# Gamma_PIN_V2.net
KiCad netlist of a schematic drawn in EAGLE
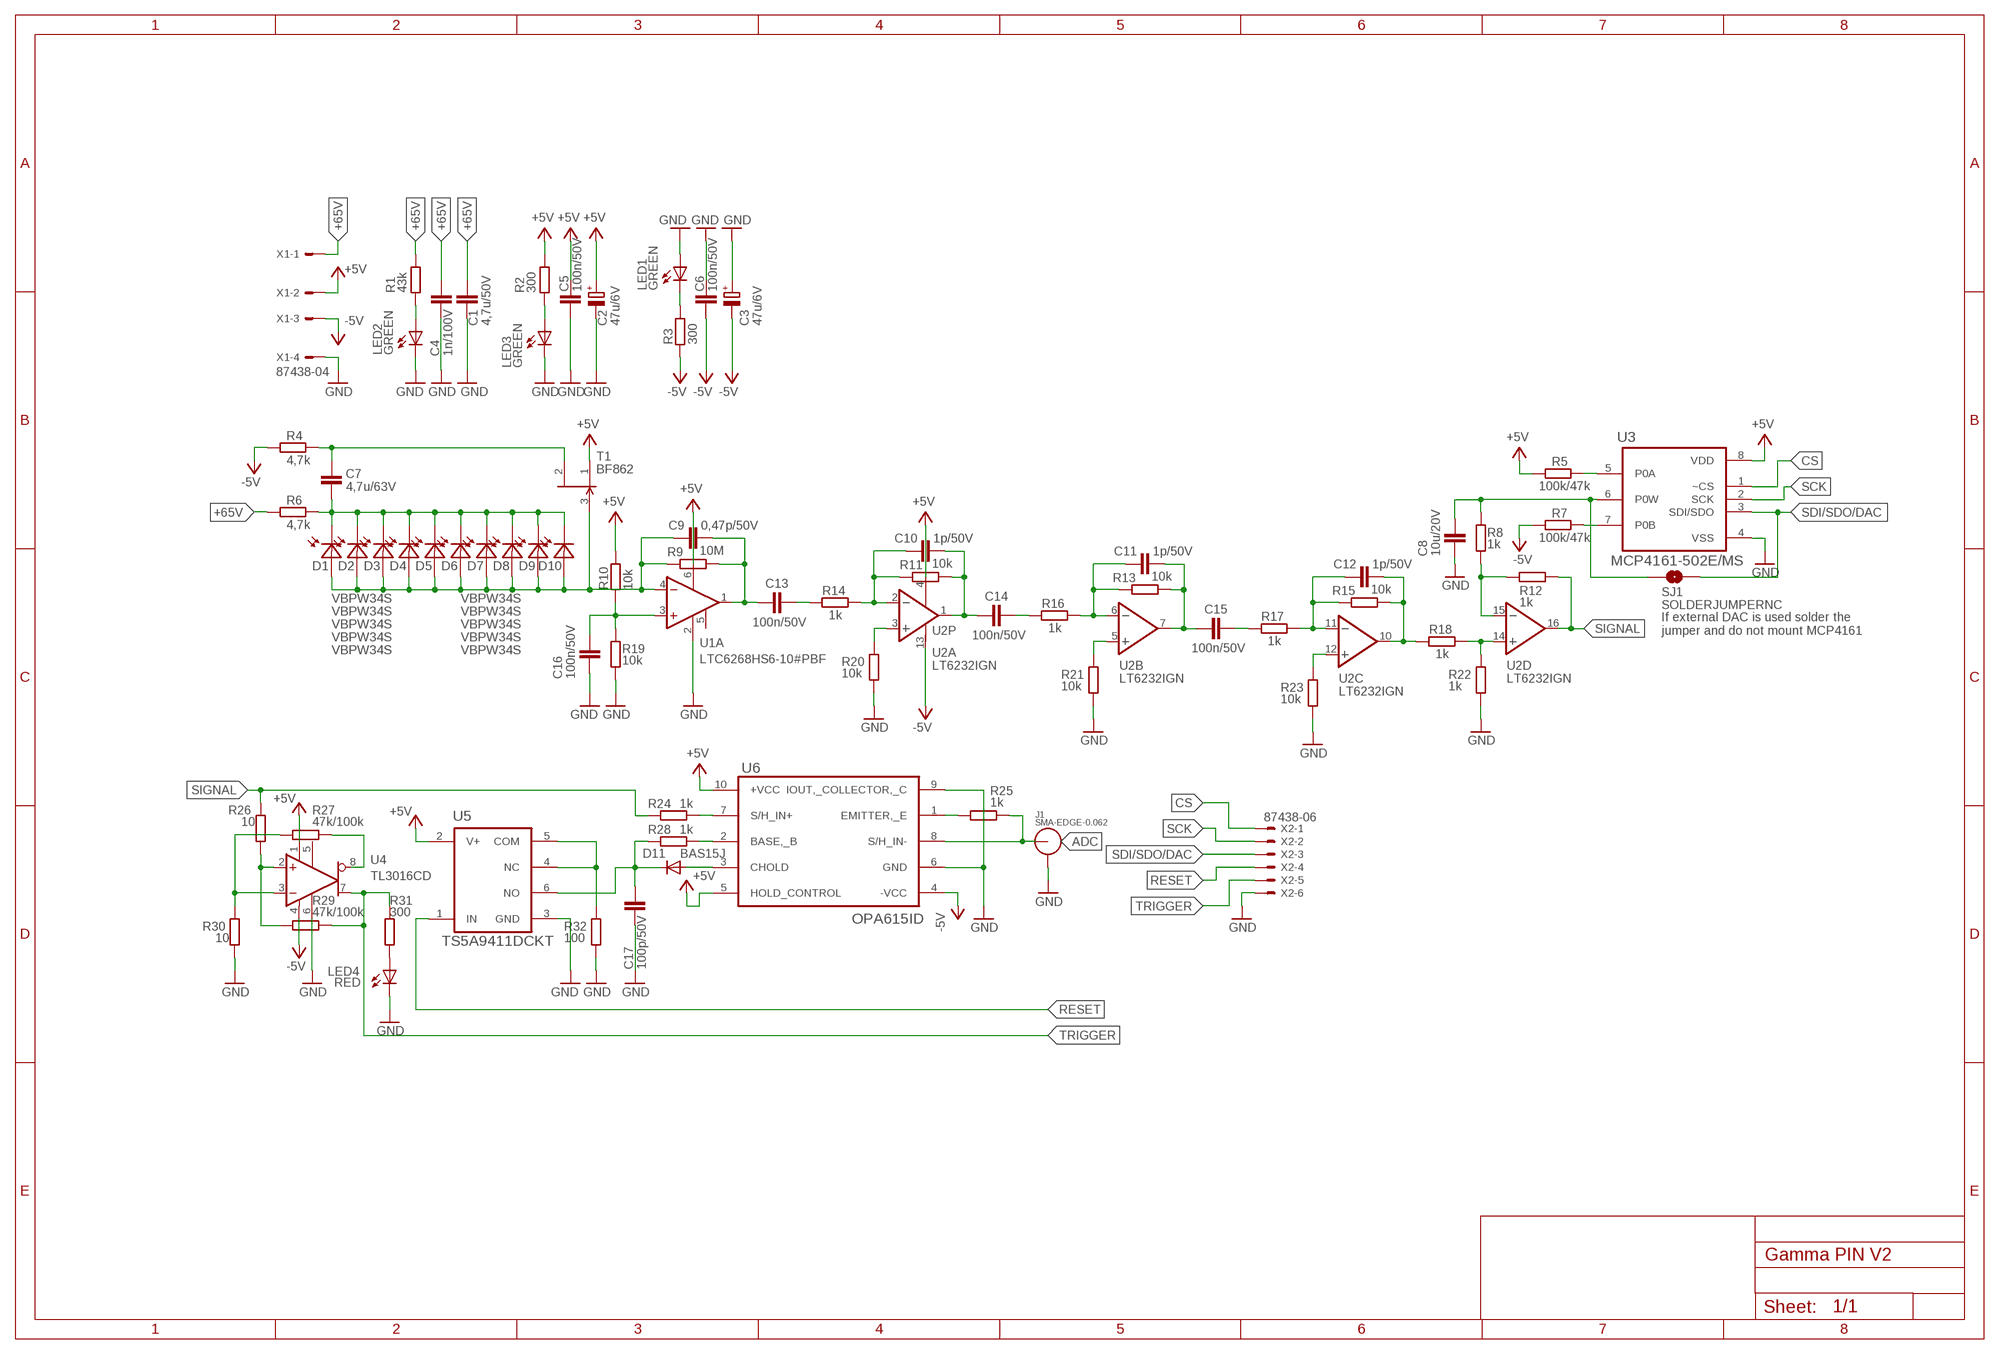
[diagram p0: schematic, sheet 1]

(export (version "E")
  (design (tool "Eeschema 10.0.6"))
  (components
    (comp (ref "C1")
      (value "4,7u/50V")
      (footprint "eagle-import:C1206")
      (libsource (lib "eagle-import") (part "rcl_334_C-EUC1206"))
    )
    (comp (ref "C2")
      (value "47u/6V")
      (footprint "eagle-import:SMC_B")
      (libsource (lib "eagle-import") (part "CPOL-EUSMCB"))
    )
    (comp (ref "C3")
      (value "47u/6V")
      (footprint "eagle-import:SMC_B")
      (libsource (lib "eagle-import") (part "CPOL-EUSMCB"))
    )
    (comp (ref "C4")
      (value "1n/100V")
      (footprint "eagle-import:C0603")
      (libsource (lib "eagle-import") (part "C-EUC0603"))
    )
    (comp (ref "C5")
      (value "100n/50V")
      (footprint "eagle-import:C0603")
      (libsource (lib "eagle-import") (part "rcl_334_C-EUC0603"))
    )
    (comp (ref "C6")
      (value "100n/50V")
      (footprint "eagle-import:C0603")
      (libsource (lib "eagle-import") (part "rcl_334_C-EUC0603"))
    )
    (comp (ref "C7")
      (value "4,7u/63V")
      (footprint "eagle-import:C1206")
      (libsource (lib "eagle-import") (part "C-EUC1206"))
    )
    (comp (ref "C8")
      (value "10u/20V")
      (footprint "eagle-import:C0603")
      (libsource (lib "eagle-import") (part "rcl_334_C-EUC0603"))
    )
    (comp (ref "C9")
      (value "0,47p/50V")
      (footprint "eagle-import:C0603")
      (libsource (lib "eagle-import") (part "rcl_334_C-EUC0603"))
    )
    (comp (ref "C10")
      (value "1p/50V")
      (footprint "eagle-import:C0603")
      (libsource (lib "eagle-import") (part "rcl_334_C-EUC0603"))
    )
    (comp (ref "C11")
      (value "1p/50V")
      (footprint "eagle-import:C0603")
      (libsource (lib "eagle-import") (part "rcl_334_C-EUC0603"))
    )
    (comp (ref "C12")
      (value "1p/50V")
      (footprint "eagle-import:C0603")
      (libsource (lib "eagle-import") (part "rcl_334_C-EUC0603"))
    )
    (comp (ref "C13")
      (value "100n/50V")
      (footprint "eagle-import:C0603")
      (libsource (lib "eagle-import") (part "rcl_334_C-EUC0603"))
    )
    (comp (ref "C14")
      (value "100n/50V")
      (footprint "eagle-import:C0603")
      (libsource (lib "eagle-import") (part "rcl_334_C-EUC0603"))
    )
    (comp (ref "C15")
      (value "100n/50V")
      (footprint "eagle-import:C0603")
      (libsource (lib "eagle-import") (part "rcl_334_C-EUC0603"))
    )
    (comp (ref "C16")
      (value "100n/50V")
      (footprint "eagle-import:C0603")
      (libsource (lib "eagle-import") (part "rcl_334_C-EUC0603"))
    )
    (comp (ref "C17")
      (value "100p/50V")
      (footprint "eagle-import:C0603")
      (libsource (lib "eagle-import") (part "rcl_334_C-EUC0603"))
    )
    (comp (ref "D1")
      (value "VBPW34S")
      (footprint "eagle-import:SOD6439X130N")
      (fields (field (name "MF") "Vishay"))
      (libsource (lib "eagle-import") (part "VBPW34S"))
    )
    (comp (ref "D2")
      (value "VBPW34S")
      (footprint "eagle-import:SOD6439X130N")
      (fields (field (name "MF") "Vishay"))
      (libsource (lib "eagle-import") (part "VBPW34S"))
    )
    (comp (ref "D3")
      (value "VBPW34S")
      (footprint "eagle-import:SOD6439X130N")
      (fields (field (name "MF") "Vishay"))
      (libsource (lib "eagle-import") (part "VBPW34S"))
    )
    (comp (ref "D4")
      (value "VBPW34S")
      (footprint "eagle-import:SOD6439X130N")
      (fields (field (name "MF") "Vishay"))
      (libsource (lib "eagle-import") (part "VBPW34S"))
    )
    (comp (ref "D5")
      (value "VBPW34S")
      (footprint "eagle-import:SOD6439X130N")
      (fields (field (name "MF") "Vishay"))
      (libsource (lib "eagle-import") (part "VBPW34S"))
    )
    (comp (ref "D6")
      (value "VBPW34S")
      (footprint "eagle-import:SOD6439X130N")
      (fields (field (name "MF") "Vishay"))
      (libsource (lib "eagle-import") (part "VBPW34S"))
    )
    (comp (ref "D7")
      (value "VBPW34S")
      (footprint "eagle-import:SOD6439X130N")
      (fields (field (name "MF") "Vishay"))
      (libsource (lib "eagle-import") (part "VBPW34S"))
    )
    (comp (ref "D8")
      (value "VBPW34S")
      (footprint "eagle-import:SOD6439X130N")
      (fields (field (name "MF") "Vishay"))
      (libsource (lib "eagle-import") (part "VBPW34S"))
    )
    (comp (ref "D9")
      (value "VBPW34S")
      (footprint "eagle-import:SOD6439X130N")
      (fields (field (name "MF") "Vishay"))
      (libsource (lib "eagle-import") (part "VBPW34S"))
    )
    (comp (ref "D10")
      (value "VBPW34S")
      (footprint "eagle-import:SOD6439X130N")
      (fields (field (name "MF") "Vishay"))
      (libsource (lib "eagle-import") (part "VBPW34S"))
    )
    (comp (ref "D11")
      (value "BAS15J")
      (footprint "eagle-import:SC79_INFINEON")
      (libsource (lib "eagle-import") (part "DIODE-SC79_INFINEON"))
    )
    (comp (ref "J1")
      (value "SMA-EDGE-0.062")
      (footprint "eagle-import:CONSMA003.062")
      (libsource (lib "eagle-import") (part "LINX-SMA-EDGE-0.062"))
    )
    (comp (ref "LED1")
      (value "GREEN")
      (footprint "eagle-import:CHIPLED_0603")
      (libsource (lib "eagle-import") (part "LEDCHIPLED_0603"))
    )
    (comp (ref "LED2")
      (value "GREEN")
      (footprint "eagle-import:CHIPLED_0603")
      (libsource (lib "eagle-import") (part "LEDCHIPLED_0603"))
    )
    (comp (ref "LED3")
      (value "GREEN")
      (footprint "eagle-import:CHIPLED_0603")
      (libsource (lib "eagle-import") (part "LEDCHIPLED_0603"))
    )
    (comp (ref "LED4")
      (value "RED")
      (footprint "eagle-import:CHIPLED_0603")
      (libsource (lib "eagle-import") (part "LEDCHIPLED_0603"))
    )
    (comp (ref "R1")
      (value "43k")
      (footprint "eagle-import:R0603")
      (libsource (lib "eagle-import") (part "R-EU_R0603"))
    )
    (comp (ref "R2")
      (value "300")
      (footprint "eagle-import:R0603")
      (libsource (lib "eagle-import") (part "R-EU_R0603"))
    )
    (comp (ref "R3")
      (value "300")
      (footprint "eagle-import:R0603")
      (libsource (lib "eagle-import") (part "R-EU_R0603"))
    )
    (comp (ref "R4")
      (value "4,7k")
      (footprint "eagle-import:R0603")
      (libsource (lib "eagle-import") (part "R-EU_R0603"))
    )
    (comp (ref "R5")
      (value "100k/47k")
      (footprint "eagle-import:R0603")
      (libsource (lib "eagle-import") (part "R-EU_R0603"))
    )
    (comp (ref "R6")
      (value "4,7k")
      (footprint "eagle-import:R0603")
      (libsource (lib "eagle-import") (part "R-EU_R0603"))
    )
    (comp (ref "R7")
      (value "100k/47k")
      (footprint "eagle-import:R0603")
      (libsource (lib "eagle-import") (part "R-EU_R0603"))
    )
    (comp (ref "R8")
      (value "1k")
      (footprint "eagle-import:R0603")
      (libsource (lib "eagle-import") (part "R-EU_R0603"))
    )
    (comp (ref "R9")
      (value "10M")
      (footprint "eagle-import:R0603")
      (libsource (lib "eagle-import") (part "R-EU_R0603"))
    )
    (comp (ref "R10")
      (value "10k")
      (footprint "eagle-import:R0603")
      (libsource (lib "eagle-import") (part "R-EU_R0603"))
    )
    (comp (ref "R11")
      (value "10k")
      (footprint "eagle-import:R0603")
      (libsource (lib "eagle-import") (part "R-EU_R0603"))
    )
    (comp (ref "R12")
      (value "1k")
      (footprint "eagle-import:R0603")
      (libsource (lib "eagle-import") (part "R-EU_R0603"))
    )
    (comp (ref "R13")
      (value "10k")
      (footprint "eagle-import:R0603")
      (libsource (lib "eagle-import") (part "R-EU_R0603"))
    )
    (comp (ref "R14")
      (value "1k")
      (footprint "eagle-import:R0603")
      (libsource (lib "eagle-import") (part "R-EU_R0603"))
    )
    (comp (ref "R15")
      (value "10k")
      (footprint "eagle-import:R0603")
      (libsource (lib "eagle-import") (part "R-EU_R0603"))
    )
    (comp (ref "R16")
      (value "1k")
      (footprint "eagle-import:R0603")
      (libsource (lib "eagle-import") (part "R-EU_R0603"))
    )
    (comp (ref "R17")
      (value "1k")
      (footprint "eagle-import:R0603")
      (libsource (lib "eagle-import") (part "R-EU_R0603"))
    )
    (comp (ref "R18")
      (value "1k")
      (footprint "eagle-import:R0603")
      (libsource (lib "eagle-import") (part "R-EU_R0603"))
    )
    (comp (ref "R19")
      (value "10k")
      (footprint "eagle-import:R0603")
      (libsource (lib "eagle-import") (part "R-EU_R0603"))
    )
    (comp (ref "R20")
      (value "10k")
      (footprint "eagle-import:R0603")
      (libsource (lib "eagle-import") (part "R-EU_R0603"))
    )
    (comp (ref "R21")
      (value "10k")
      (footprint "eagle-import:R0603")
      (libsource (lib "eagle-import") (part "R-EU_R0603"))
    )
    (comp (ref "R22")
      (value "1k")
      (footprint "eagle-import:R0603")
      (libsource (lib "eagle-import") (part "R-EU_R0603"))
    )
    (comp (ref "R23")
      (value "10k")
      (footprint "eagle-import:R0603")
      (libsource (lib "eagle-import") (part "R-EU_R0603"))
    )
    (comp (ref "R24")
      (value "1k")
      (footprint "eagle-import:R0603")
      (libsource (lib "eagle-import") (part "R-EU_R0603"))
    )
    (comp (ref "R25")
      (value "1k")
      (footprint "eagle-import:R0603")
      (libsource (lib "eagle-import") (part "R-EU_R0603"))
    )
    (comp (ref "R26")
      (value "10")
      (footprint "eagle-import:R0603")
      (libsource (lib "eagle-import") (part "R-EU_R0603"))
    )
    (comp (ref "R27")
      (value "47k/100k")
      (footprint "eagle-import:R0603")
      (libsource (lib "eagle-import") (part "R-EU_R0603"))
    )
    (comp (ref "R28")
      (value "1k")
      (footprint "eagle-import:R0603")
      (libsource (lib "eagle-import") (part "R-EU_R0603"))
    )
    (comp (ref "R29")
      (value "47k/100k")
      (footprint "eagle-import:R0603")
      (libsource (lib "eagle-import") (part "R-EU_R0603"))
    )
    (comp (ref "R30")
      (value "10")
      (footprint "eagle-import:R0603")
      (libsource (lib "eagle-import") (part "R-EU_R0603"))
    )
    (comp (ref "R31")
      (value "300")
      (footprint "eagle-import:R0603")
      (libsource (lib "eagle-import") (part "R-EU_R0603"))
    )
    (comp (ref "R32")
      (value "100")
      (footprint "eagle-import:R0603")
      (libsource (lib "eagle-import") (part "R-EU_R0603"))
    )
    (comp (ref "SJ1")
      (value "SOLDERJUMPERNC")
      (footprint "eagle-import:SJ_2S_SMALL")
      (libsource (lib "eagle-import") (part "SOLDERJUMPERNC"))
    )
    (comp (ref "T1")
      (value "BF862")
      (footprint "eagle-import:SOT23")
      (fields (field (name "MF") "NXP Semiconductors"))
      (libsource (lib "eagle-import") (part "BF862"))
    )
    (comp (ref "U1")
      (value "LTC6268HS6-10#PBF")
      (footprint "eagle-import:TSOT23-6")
      (libsource (lib "eagle-import") (part "LTC6268HS6-10#PBFTSOT-23"))
    )
    (comp (ref "U2")
      (value "LT6232IGN")
      (footprint "eagle-import:SSOP16")
      (libsource (lib "eagle-import") (part "LT6232GNI"))
    )
    (comp (ref "U3")
      (value "MCP4161-502E/MS")
      (footprint "eagle-import:MSOP8")
      (libsource (lib "eagle-import") (part "MCP4161-502E/MS"))
    )
    (comp (ref "U4")
      (value "TL3016CD")
      (footprint "eagle-import:TSSOP8")
      (libsource (lib "eagle-import") (part "TL3016CD"))
    )
    (comp (ref "U5")
      (value "TS5A9411DCKT")
      (footprint "eagle-import:SOT65P210X110-6N")
      (libsource (lib "eagle-import") (part "TS5A9411DCKT"))
    )
    (comp (ref "U6")
      (value "OPA615ID")
      (footprint "eagle-import:MSOP10")
      (libsource (lib "eagle-import") (part "OPA615ID"))
    )
    (comp (ref "X1")
      (value "87438-04")
      (footprint "eagle-import:87438-04")
      (fields (field (name "MF") "MOLEX"))
      (libsource (lib "eagle-import") (part "87438-04"))
    )
    (comp (ref "X2")
      (value "87438-06")
      (footprint "eagle-import:87438-06")
      (fields (field (name "MF") "MOLEX") (field (name "MPN") "87438-0643"))
      (libsource (lib "eagle-import") (part "87438-06"))
    )
  )
  (nets
    (net (code "1") (name "+5V") (class "Default")
      (node (ref "C2") (pin "+") (pinfunction "+_+") (pintype "passive"))
      (node (ref "C5") (pin "2") (pinfunction "2_2") (pintype "passive"))
      (node (ref "R10") (pin "2") (pinfunction "2_2") (pintype "passive"))
      (node (ref "R2") (pin "2") (pinfunction "2_2") (pintype "passive"))
      (node (ref "R5") (pin "1") (pinfunction "1_1") (pintype "passive"))
      (node (ref "T1") (pin "1") (pinfunction "S_1") (pintype "passive"))
      (node (ref "U1") (pin "6") (pinfunction "VDD_6") (pintype "power_in"))
      (node (ref "U2") (pin "4") (pinfunction "V+_4") (pintype "power_in"))
      (node (ref "U3") (pin "8") (pinfunction "VDD_8") (pintype "power_in"))
      (node (ref "U4") (pin "1") (pinfunction "V+_1") (pintype "power_in"))
      (node (ref "U5") (pin "2") (pinfunction "V+_2") (pintype "power_in"))
      (node (ref "U6") (pin "10") (pinfunction "+VCC_10") (pintype "power_in"))
      (node (ref "U6") (pin "5") (pinfunction "HOLD_CONTROL_5") (pintype "input"))
      (node (ref "X1") (pin "2") (pinfunction "S_2") (pintype "passive"))
    )
    (net (code "2") (name "+65V") (class "Default")
      (node (ref "C1") (pin "1") (pinfunction "1_1") (pintype "passive"))
      (node (ref "C4") (pin "2") (pinfunction "2_2") (pintype "passive"))
      (node (ref "R1") (pin "2") (pinfunction "2_2") (pintype "passive"))
      (node (ref "R6") (pin "1") (pinfunction "1_1") (pintype "passive"))
      (node (ref "X1") (pin "1") (pinfunction "S_1") (pintype "passive"))
    )
    (net (code "3") (name "-5V") (class "Default")
      (node (ref "C3") (pin "-") (pinfunction "-_-") (pintype "passive"))
      (node (ref "C6") (pin "1") (pinfunction "1_1") (pintype "passive"))
      (node (ref "R3") (pin "1") (pinfunction "1_1") (pintype "passive"))
      (node (ref "R4") (pin "1") (pinfunction "1_1") (pintype "passive"))
      (node (ref "R7") (pin "1") (pinfunction "1_1") (pintype "passive"))
      (node (ref "U2") (pin "13") (pinfunction "V-_13") (pintype "power_in"))
      (node (ref "U4") (pin "4") (pinfunction "V-_4") (pintype "power_in"))
      (node (ref "U6") (pin "4") (pinfunction "-VCC_4") (pintype "power_in"))
      (node (ref "X1") (pin "3") (pinfunction "S_3") (pintype "passive"))
    )
    (net (code "4") (name "ADC") (class "Default")
      (node (ref "J1") (pin "ANT") (pinfunction "ANT_ANT") (pintype "bidirectional"))
      (node (ref "R25") (pin "1") (pinfunction "1_1") (pintype "passive"))
      (node (ref "U6") (pin "8") (pinfunction "S/H_IN-_8") (pintype "passive"))
    )
    (net (code "5") (name "CS") (class "Default")
      (node (ref "U3") (pin "1") (pinfunction "~{CS}_1") (pintype "input"))
      (node (ref "X2") (pin "1") (pinfunction "S_1") (pintype "passive"))
    )
    (net (code "6") (name "GND") (class "Default")
      (node (ref "C1") (pin "2") (pinfunction "2_2") (pintype "passive"))
      (node (ref "C16") (pin "1") (pinfunction "1_1") (pintype "passive"))
      (node (ref "C17") (pin "1") (pinfunction "1_1") (pintype "passive"))
      (node (ref "C2") (pin "-") (pinfunction "-_-") (pintype "passive"))
      (node (ref "C3") (pin "+") (pinfunction "+_+") (pintype "passive"))
      (node (ref "C4") (pin "1") (pinfunction "1_1") (pintype "passive"))
      (node (ref "C5") (pin "1") (pinfunction "1_1") (pintype "passive"))
      (node (ref "C6") (pin "2") (pinfunction "2_2") (pintype "passive"))
      (node (ref "C8") (pin "2") (pinfunction "2_2") (pintype "passive"))
      (node (ref "J1") (pin "GND1") (pinfunction "P$2_GND1") (pintype "bidirectional"))
      (node (ref "J1") (pin "GND2") (pinfunction "P$2_GND2") (pintype "bidirectional"))
      (node (ref "J1") (pin "GND3") (pinfunction "P$2_GND3") (pintype "bidirectional"))
      (node (ref "J1") (pin "GND4") (pinfunction "P$2_GND4") (pintype "bidirectional"))
      (node (ref "LED1") (pin "A") (pinfunction "A_A") (pintype "passive"))
      (node (ref "LED2") (pin "C") (pinfunction "C_C") (pintype "passive"))
      (node (ref "LED3") (pin "C") (pinfunction "C_C") (pintype "passive"))
      (node (ref "LED4") (pin "C") (pinfunction "C_C") (pintype "passive"))
      (node (ref "R19") (pin "1") (pinfunction "1_1") (pintype "passive"))
      (node (ref "R20") (pin "2") (pinfunction "2_2") (pintype "passive"))
      (node (ref "R21") (pin "2") (pinfunction "2_2") (pintype "passive"))
      (node (ref "R22") (pin "2") (pinfunction "2_2") (pintype "passive"))
      (node (ref "R23") (pin "2") (pinfunction "2_2") (pintype "passive"))
      (node (ref "R30") (pin "1") (pinfunction "1_1") (pintype "passive"))
      (node (ref "R32") (pin "2") (pinfunction "2_2") (pintype "passive"))
      (node (ref "U1") (pin "2") (pinfunction "GND_2") (pintype "power_in"))
      (node (ref "U3") (pin "4") (pinfunction "VSS_4") (pintype "power_in"))
      (node (ref "U4") (pin "6") (pinfunction "GND_6") (pintype "passive"))
      (node (ref "U5") (pin "3") (pinfunction "GND_3") (pintype "passive"))
      (node (ref "U6") (pin "6") (pinfunction "GND_6") (pintype "passive"))
      (node (ref "U6") (pin "9") (pinfunction "IOUT,_COLLECTOR,_C_9") (pintype "output"))
      (node (ref "X1") (pin "4") (pinfunction "S_4") (pintype "passive"))
      (node (ref "X2") (pin "6") (pinfunction "S_6") (pintype "passive"))
    )
    (net (code "7") (name "Net-(C7-Pad1)") (class "Default")
      (node (ref "C7") (pin "1") (pinfunction "1_1") (pintype "passive"))
      (node (ref "D1") (pin "C") (pinfunction "C_C") (pintype "passive"))
      (node (ref "D10") (pin "C") (pinfunction "C_C") (pintype "passive"))
      (node (ref "D2") (pin "C") (pinfunction "C_C") (pintype "passive"))
      (node (ref "D3") (pin "C") (pinfunction "C_C") (pintype "passive"))
      (node (ref "D4") (pin "C") (pinfunction "C_C") (pintype "passive"))
      (node (ref "D5") (pin "C") (pinfunction "C_C") (pintype "passive"))
      (node (ref "D6") (pin "C") (pinfunction "C_C") (pintype "passive"))
      (node (ref "D7") (pin "C") (pinfunction "C_C") (pintype "passive"))
      (node (ref "D8") (pin "C") (pinfunction "C_C") (pintype "passive"))
      (node (ref "D9") (pin "C") (pinfunction "C_C") (pintype "passive"))
      (node (ref "R6") (pin "2") (pinfunction "2_2") (pintype "passive"))
    )
    (net (code "8") (name "Net-(C13-Pad1)") (class "Default")
      (node (ref "C13") (pin "1") (pinfunction "1_1") (pintype "passive"))
      (node (ref "R14") (pin "2") (pinfunction "2_2") (pintype "passive"))
    )
    (net (code "9") (name "Net-(C14-Pad1)") (class "Default")
      (node (ref "C14") (pin "1") (pinfunction "1_1") (pintype "passive"))
      (node (ref "R16") (pin "2") (pinfunction "2_2") (pintype "passive"))
    )
    (net (code "10") (name "Net-(C15-Pad1)") (class "Default")
      (node (ref "C15") (pin "1") (pinfunction "1_1") (pintype "passive"))
      (node (ref "R17") (pin "2") (pinfunction "2_2") (pintype "passive"))
    )
    (net (code "11") (name "Net-(LED1-PadC)") (class "Default")
      (node (ref "LED1") (pin "C") (pinfunction "C_C") (pintype "passive"))
      (node (ref "R3") (pin "2") (pinfunction "2_2") (pintype "passive"))
    )
    (net (code "12") (name "Net-(LED2-PadA)") (class "Default")
      (node (ref "LED2") (pin "A") (pinfunction "A_A") (pintype "passive"))
      (node (ref "R1") (pin "1") (pinfunction "1_1") (pintype "passive"))
    )
    (net (code "13") (name "Net-(LED3-PadA)") (class "Default")
      (node (ref "LED3") (pin "A") (pinfunction "A_A") (pintype "passive"))
      (node (ref "R2") (pin "1") (pinfunction "1_1") (pintype "passive"))
    )
    (net (code "14") (name "Net-(LED4-PadA)") (class "Default")
      (node (ref "LED4") (pin "A") (pinfunction "A_A") (pintype "passive"))
      (node (ref "R31") (pin "1") (pinfunction "1_1") (pintype "passive"))
    )
    (net (code "15") (name "Net-(T1-D)") (class "Default")
      (node (ref "C7") (pin "2") (pinfunction "2_2") (pintype "passive"))
      (node (ref "R4") (pin "2") (pinfunction "2_2") (pintype "passive"))
      (node (ref "T1") (pin "2") (pinfunction "D_2") (pintype "passive"))
    )
    (net (code "16") (name "Net-(T1-G)") (class "Default")
      (node (ref "C9") (pin "2") (pinfunction "2_2") (pintype "passive"))
      (node (ref "D1") (pin "A") (pinfunction "A_A") (pintype "passive"))
      (node (ref "D10") (pin "A") (pinfunction "A_A") (pintype "passive"))
      (node (ref "D2") (pin "A") (pinfunction "A_A") (pintype "passive"))
      (node (ref "D3") (pin "A") (pinfunction "A_A") (pintype "passive"))
      (node (ref "D4") (pin "A") (pinfunction "A_A") (pintype "passive"))
      (node (ref "D5") (pin "A") (pinfunction "A_A") (pintype "passive"))
      (node (ref "D6") (pin "A") (pinfunction "A_A") (pintype "passive"))
      (node (ref "D7") (pin "A") (pinfunction "A_A") (pintype "passive"))
      (node (ref "D8") (pin "A") (pinfunction "A_A") (pintype "passive"))
      (node (ref "D9") (pin "A") (pinfunction "A_A") (pintype "passive"))
      (node (ref "R9") (pin "2") (pinfunction "2_2") (pintype "passive"))
      (node (ref "T1") (pin "3") (pinfunction "G_3") (pintype "passive"))
      (node (ref "U1") (pin "4") (pinfunction "-IN_4") (pintype "input"))
    )
    (net (code "17") (name "Net-(U1A-+IN)") (class "Default")
      (node (ref "C16") (pin "2") (pinfunction "2_2") (pintype "passive"))
      (node (ref "R10") (pin "1") (pinfunction "1_1") (pintype "passive"))
      (node (ref "R19") (pin "2") (pinfunction "2_2") (pintype "passive"))
      (node (ref "U1") (pin "3") (pinfunction "+IN_3") (pintype "input"))
    )
    (net (code "18") (name "Net-(U1A-OUT)") (class "Default")
      (node (ref "C13") (pin "2") (pinfunction "2_2") (pintype "passive"))
      (node (ref "C9") (pin "1") (pinfunction "1_1") (pintype "passive"))
      (node (ref "R9") (pin "1") (pinfunction "1_1") (pintype "passive"))
      (node (ref "U1") (pin "1") (pinfunction "OUT_1") (pintype "output"))
    )
    (net (code "19") (name "Net-(U2A-+IN)") (class "Default")
      (node (ref "R20") (pin "1") (pinfunction "1_1") (pintype "passive"))
      (node (ref "U2") (pin "3") (pinfunction "+IN_3") (pintype "input"))
    )
    (net (code "20") (name "Net-(U2A--IN)") (class "Default")
      (node (ref "C10") (pin "2") (pinfunction "2_2") (pintype "passive"))
      (node (ref "R11") (pin "2") (pinfunction "2_2") (pintype "passive"))
      (node (ref "R14") (pin "1") (pinfunction "1_1") (pintype "passive"))
      (node (ref "U2") (pin "2") (pinfunction "-IN_2") (pintype "input"))
    )
    (net (code "21") (name "Net-(U2A-OUT)") (class "Default")
      (node (ref "C10") (pin "1") (pinfunction "1_1") (pintype "passive"))
      (node (ref "C14") (pin "2") (pinfunction "2_2") (pintype "passive"))
      (node (ref "R11") (pin "1") (pinfunction "1_1") (pintype "passive"))
      (node (ref "U2") (pin "1") (pinfunction "OUT_1") (pintype "output"))
    )
    (net (code "22") (name "Net-(U2B-+IN)") (class "Default")
      (node (ref "R21") (pin "1") (pinfunction "1_1") (pintype "passive"))
      (node (ref "U2") (pin "5") (pinfunction "+IN_5") (pintype "input"))
    )
    (net (code "23") (name "Net-(U2B--IN)") (class "Default")
      (node (ref "C11") (pin "2") (pinfunction "2_2") (pintype "passive"))
      (node (ref "R13") (pin "2") (pinfunction "2_2") (pintype "passive"))
      (node (ref "R16") (pin "1") (pinfunction "1_1") (pintype "passive"))
      (node (ref "U2") (pin "6") (pinfunction "-IN_6") (pintype "input"))
    )
    (net (code "24") (name "Net-(U2B-OUT)") (class "Default")
      (node (ref "C11") (pin "1") (pinfunction "1_1") (pintype "passive"))
      (node (ref "C15") (pin "2") (pinfunction "2_2") (pintype "passive"))
      (node (ref "R13") (pin "1") (pinfunction "1_1") (pintype "passive"))
      (node (ref "U2") (pin "7") (pinfunction "OUT_7") (pintype "output"))
    )
    (net (code "25") (name "Net-(U2C-+IN)") (class "Default")
      (node (ref "R23") (pin "1") (pinfunction "1_1") (pintype "passive"))
      (node (ref "U2") (pin "12") (pinfunction "+IN_12") (pintype "input"))
    )
    (net (code "26") (name "Net-(U2C--IN)") (class "Default")
      (node (ref "C12") (pin "2") (pinfunction "2_2") (pintype "passive"))
      (node (ref "R15") (pin "2") (pinfunction "2_2") (pintype "passive"))
      (node (ref "R17") (pin "1") (pinfunction "1_1") (pintype "passive"))
      (node (ref "U2") (pin "11") (pinfunction "-IN_11") (pintype "input"))
    )
    (net (code "27") (name "Net-(U2C-OUT)") (class "Default")
      (node (ref "C12") (pin "1") (pinfunction "1_1") (pintype "passive"))
      (node (ref "R15") (pin "1") (pinfunction "1_1") (pintype "passive"))
      (node (ref "R18") (pin "2") (pinfunction "2_2") (pintype "passive"))
      (node (ref "U2") (pin "10") (pinfunction "OUT_10") (pintype "output"))
    )
    (net (code "28") (name "Net-(U2D-+IN)") (class "Default")
      (node (ref "R18") (pin "1") (pinfunction "1_1") (pintype "passive"))
      (node (ref "R22") (pin "1") (pinfunction "1_1") (pintype "passive"))
      (node (ref "U2") (pin "14") (pinfunction "+IN_14") (pintype "input"))
    )
    (net (code "29") (name "Net-(U2D--IN)") (class "Default")
      (node (ref "R12") (pin "2") (pinfunction "2_2") (pintype "passive"))
      (node (ref "R8") (pin "2") (pinfunction "2_2") (pintype "passive"))
      (node (ref "U2") (pin "15") (pinfunction "-IN_15") (pintype "input"))
    )
    (net (code "30") (name "Net-(U3-P0A)") (class "Default")
      (node (ref "R5") (pin "2") (pinfunction "2_2") (pintype "passive"))
      (node (ref "U3") (pin "5") (pinfunction "P0A_5") (pintype "passive"))
    )
    (net (code "31") (name "Net-(U3-P0B)") (class "Default")
      (node (ref "R7") (pin "2") (pinfunction "2_2") (pintype "passive"))
      (node (ref "U3") (pin "7") (pinfunction "P0B_7") (pintype "passive"))
    )
    (net (code "32") (name "Net-(U3-P0W)") (class "Default")
      (node (ref "C8") (pin "1") (pinfunction "1_1") (pintype "passive"))
      (node (ref "R8") (pin "1") (pinfunction "1_1") (pintype "passive"))
      (node (ref "SJ1") (pin "1") (pinfunction "1_1") (pintype "passive"))
      (node (ref "U3") (pin "6") (pinfunction "P0W_6") (pintype "passive"))
    )
    (net (code "33") (name "Net-(U4-*QOUT)") (class "Default")
      (node (ref "R27") (pin "1") (pinfunction "1_1") (pintype "passive"))
      (node (ref "U4") (pin "8") (pinfunction "*QOUT_8") (pintype "passive"))
    )
    (net (code "34") (name "Net-(U4-+IN)") (class "Default")
      (node (ref "R26") (pin "2") (pinfunction "2_2") (pintype "passive"))
      (node (ref "R29") (pin "2") (pinfunction "2_2") (pintype "passive"))
      (node (ref "U4") (pin "2") (pinfunction "+IN_2") (pintype "input"))
    )
    (net (code "35") (name "Net-(U4--IN)") (class "Default")
      (node (ref "R27") (pin "2") (pinfunction "2_2") (pintype "passive"))
      (node (ref "R30") (pin "2") (pinfunction "2_2") (pintype "passive"))
      (node (ref "U4") (pin "3") (pinfunction "-IN_3") (pintype "input"))
    )
    (net (code "36") (name "Net-(U5-COM)") (class "Default")
      (node (ref "R32") (pin "1") (pinfunction "1_1") (pintype "passive"))
      (node (ref "U5") (pin "4") (pinfunction "NC_4") (pintype "input"))
      (node (ref "U5") (pin "5") (pinfunction "COM_5") (pintype "output"))
    )
    (net (code "37") (name "Net-(U5-NO)") (class "Default")
      (node (ref "C17") (pin "2") (pinfunction "2_2") (pintype "passive"))
      (node (ref "D11") (pin "C") (pinfunction "C_C") (pintype "passive"))
      (node (ref "R28") (pin "2") (pinfunction "2_2") (pintype "passive"))
      (node (ref "U5") (pin "6") (pinfunction "NO_6") (pintype "input"))
    )
    (net (code "38") (name "Net-(U6-BASE,_B)") (class "Default")
      (node (ref "R28") (pin "1") (pinfunction "1_1") (pintype "passive"))
      (node (ref "U6") (pin "2") (pinfunction "BASE,_B_2") (pintype "input"))
    )
    (net (code "39") (name "Net-(U6-CHOLD)") (class "Default")
      (node (ref "D11") (pin "A") (pinfunction "A_A") (pintype "passive"))
      (node (ref "U6") (pin "3") (pinfunction "CHOLD_3") (pintype "input"))
    )
    (net (code "40") (name "Net-(U6-EMITTER,_E)") (class "Default")
      (node (ref "R25") (pin "2") (pinfunction "2_2") (pintype "passive"))
      (node (ref "U6") (pin "1") (pinfunction "EMITTER,_E_1") (pintype "input"))
    )
    (net (code "41") (name "Net-(U6-S{slash}H_IN+)") (class "Default")
      (node (ref "R24") (pin "1") (pinfunction "1_1") (pintype "passive"))
      (node (ref "U6") (pin "7") (pinfunction "S/H_IN+_7") (pintype "passive"))
    )
    (net (code "42") (name "RESET") (class "Default")
      (node (ref "U5") (pin "1") (pinfunction "IN_1") (pintype "input"))
      (node (ref "X2") (pin "4") (pinfunction "S_4") (pintype "passive"))
    )
    (net (code "43") (name "SCK") (class "Default")
      (node (ref "U3") (pin "2") (pinfunction "SCK_2") (pintype "input"))
      (node (ref "X2") (pin "2") (pinfunction "S_2") (pintype "passive"))
    )
    (net (code "44") (name "SDI{slash}SDO{slash}DAC") (class "Default")
      (node (ref "SJ1") (pin "2") (pinfunction "2_2") (pintype "passive"))
      (node (ref "U3") (pin "3") (pinfunction "SDI/SDO_3") (pintype "bidirectional"))
      (node (ref "X2") (pin "3") (pinfunction "S_3") (pintype "passive"))
    )
    (net (code "45") (name "SIGNAL") (class "Default")
      (node (ref "R12") (pin "1") (pinfunction "1_1") (pintype "passive"))
      (node (ref "R24") (pin "2") (pinfunction "2_2") (pintype "passive"))
      (node (ref "R26") (pin "1") (pinfunction "1_1") (pintype "passive"))
      (node (ref "U2") (pin "16") (pinfunction "OUT_16") (pintype "output"))
    )
    (net (code "46") (name "TRIGGER") (class "Default")
      (node (ref "R29") (pin "1") (pinfunction "1_1") (pintype "passive"))
      (node (ref "R31") (pin "2") (pinfunction "2_2") (pintype "passive"))
      (node (ref "U4") (pin "7") (pinfunction "QOUT_7") (pintype "output"))
      (node (ref "X2") (pin "5") (pinfunction "S_5") (pintype "passive"))
    )
    (net (code "47") (name "unconnected-(U1A-SHDN-Pad5)") (class "Default")
      (node (ref "U1") (pin "5") (pinfunction "SHDN_5") (pintype "bidirectional"))
    )
    (net (code "48") (name "unconnected-(U4-LATCH-Pad5)") (class "Default")
      (node (ref "U4") (pin "5") (pinfunction "LATCH_5") (pintype "passive"))
    )
  )
)
